# Sensors.net
KiCad netlist of a schematic drawn in Altium Designer
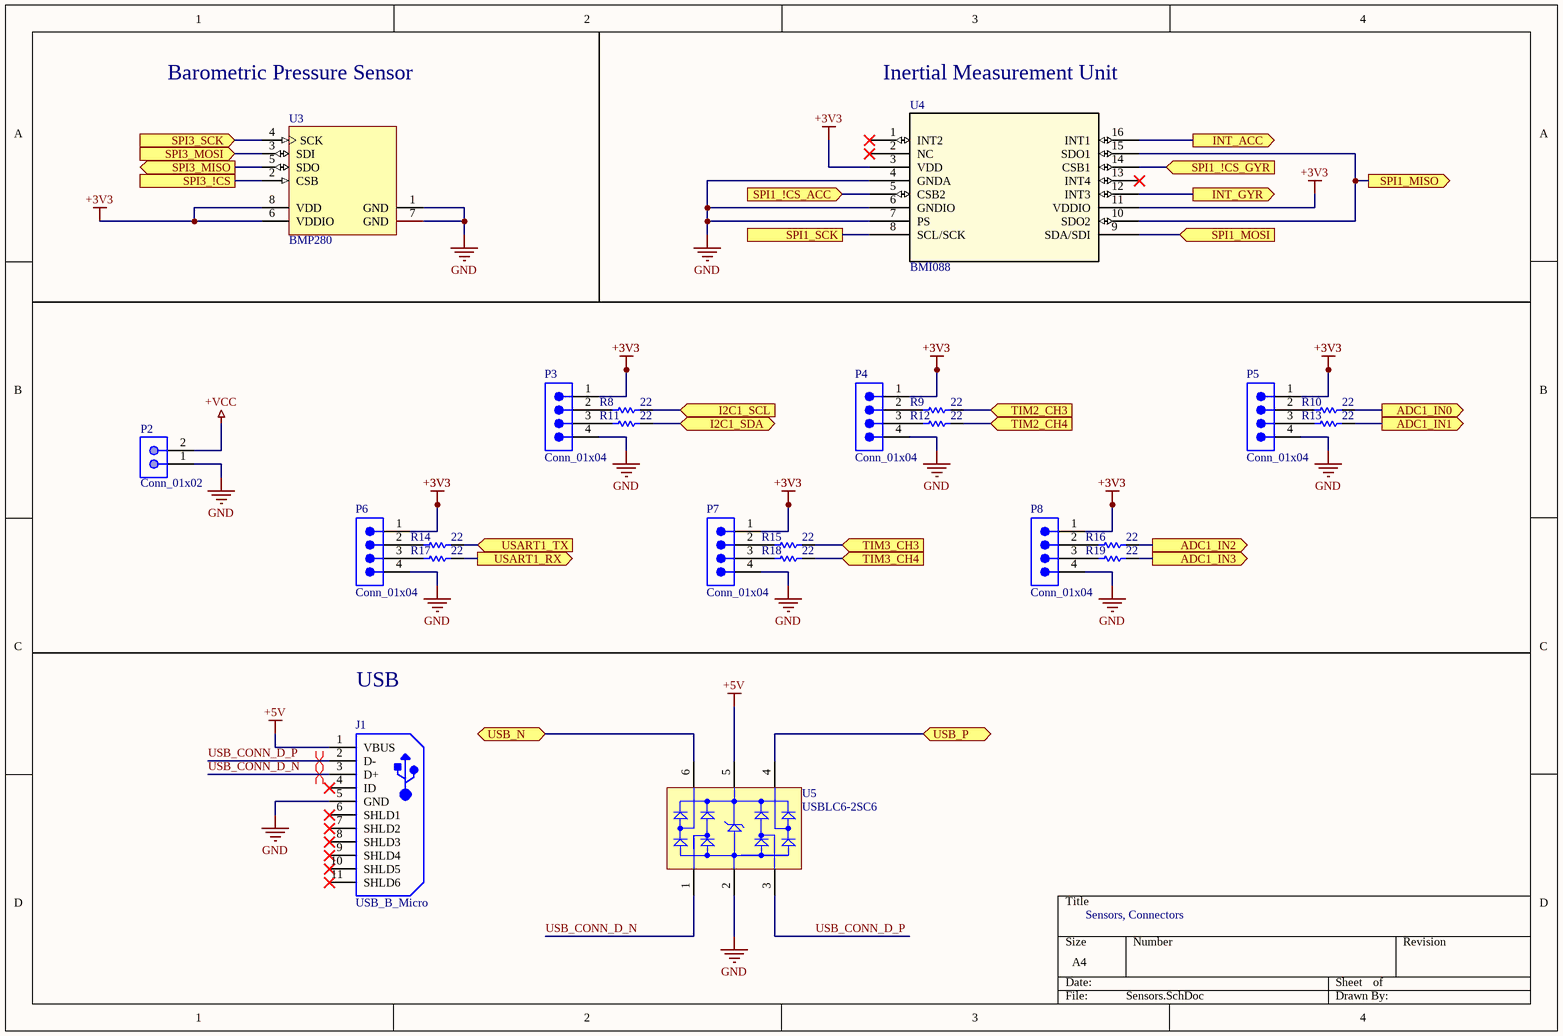
[diagram p0: Sensors.SchDoc]

(export (version "E")
  (design (tool "Eeschema 10.0.6"))
  (components
    (comp (ref "J1")
      (value "USB_B_Micro")
      (footprint "MOLX-105133-0001_V")
      (description "Micro USB B Type Receptacle, -55 to 85 degC, 5-Pin SMD, RoHS, Tape and Reel")
      (fields
        (field (name "MANUFACTURER") "Amphenol FCI")
        (field (name "MANUFACTURER PART NUMBER") "10118193-0001LF")
      )
      (libsource (lib "F4_Flight_Controller") (part "USB_B_Micro"))
    )
    (comp (ref "P2")
      (value "Conn_01x02")
      (footprint "HDRV10W90P254_1X2_1270X483X840P")
      (fields
        (field (name "MANUFACTURER") "TE Connectivity")
        (field (name "MANUFACTURER PART NUMBER") "5-146280-2")
      )
      (libsource (lib "F4_Flight_Controller") (part "Male Header 01x02"))
    )
    (comp (ref "P3")
      (value "Conn_01x04")
      (footprint "HDRV10W90P254_1X4_1270X483X840P")
      (description "Horizontal Surface Mount Header, -55 to 125 degC, 2 mm Pitch, 4-Pin, Male, RoHS")
      (fields (field (name "PARTNUMBER") "MMT-104-01-L-SH") (field (name "MANUFACTURER") "Samtec"))
      (libsource (lib "F4_Flight_Controller") (part "Male Header 01x04"))
    )
    (comp (ref "P4")
      (value "Conn_01x04")
      (footprint "HDRV10W90P254_1X4_1270X483X840P")
      (description "Horizontal Surface Mount Header, -55 to 125 degC, 2 mm Pitch, 4-Pin, Male, RoHS")
      (fields (field (name "PARTNUMBER") "MMT-104-01-L-SH") (field (name "MANUFACTURER") "Samtec"))
      (libsource (lib "F4_Flight_Controller") (part "Male Header 01x04"))
    )
    (comp (ref "P5")
      (value "Conn_01x04")
      (footprint "HDRV10W90P254_1X4_1270X483X840P")
      (description "Horizontal Surface Mount Header, -55 to 125 degC, 2 mm Pitch, 4-Pin, Male, RoHS")
      (fields (field (name "PARTNUMBER") "MMT-104-01-L-SH") (field (name "MANUFACTURER") "Samtec"))
      (libsource (lib "F4_Flight_Controller") (part "Male Header 01x04"))
    )
    (comp (ref "P6")
      (value "Conn_01x04")
      (footprint "HDRV10W90P254_1X4_1270X483X840P")
      (description "Horizontal Surface Mount Header, -55 to 125 degC, 2 mm Pitch, 4-Pin, Male, RoHS")
      (fields (field (name "PARTNUMBER") "MMT-104-01-L-SH") (field (name "MANUFACTURER") "Samtec"))
      (libsource (lib "F4_Flight_Controller") (part "Male Header 01x04"))
    )
    (comp (ref "P7")
      (value "Conn_01x04")
      (footprint "HDRV10W90P254_1X4_1270X483X840P")
      (description "Horizontal Surface Mount Header, -55 to 125 degC, 2 mm Pitch, 4-Pin, Male, RoHS")
      (fields (field (name "PARTNUMBER") "MMT-104-01-L-SH") (field (name "MANUFACTURER") "Samtec"))
      (libsource (lib "F4_Flight_Controller") (part "Male Header 01x04"))
    )
    (comp (ref "P8")
      (value "Conn_01x04")
      (footprint "HDRV10W90P254_1X4_1270X483X840P")
      (description "Horizontal Surface Mount Header, -55 to 125 degC, 2 mm Pitch, 4-Pin, Male, RoHS")
      (fields (field (name "PARTNUMBER") "MMT-104-01-L-SH") (field (name "MANUFACTURER") "Samtec"))
      (libsource (lib "F4_Flight_Controller") (part "Male Header 01x04"))
    )
    (comp (ref "R8")
      (value "22")
      (footprint "Resistor 0402")
      (description "Chip Resistor 0402")
      (fields (field (name "MANUFACTURER") "Vishay") (field (name "PART NUMBER") "CRCW0402120RFKED"))
      (libsource (lib "F4_Flight_Controller") (part "Resistor 0402"))
    )
    (comp (ref "R9")
      (value "22")
      (footprint "Resistor 0402")
      (description "Chip Resistor 0402")
      (fields (field (name "MANUFACTURER") "Vishay") (field (name "PART NUMBER") "CRCW0402120RFKED"))
      (libsource (lib "F4_Flight_Controller") (part "Resistor 0402"))
    )
    (comp (ref "R10")
      (value "22")
      (footprint "Resistor 0402")
      (description "Chip Resistor 0402")
      (fields (field (name "MANUFACTURER") "Vishay") (field (name "PART NUMBER") "CRCW0402120RFKED"))
      (libsource (lib "F4_Flight_Controller") (part "Resistor 0402"))
    )
    (comp (ref "R11")
      (value "22")
      (footprint "Resistor 0402")
      (description "Chip Resistor 0402")
      (fields (field (name "MANUFACTURER") "Vishay") (field (name "PART NUMBER") "CRCW0402120RFKED"))
      (libsource (lib "F4_Flight_Controller") (part "Resistor 0402"))
    )
    (comp (ref "R12")
      (value "22")
      (footprint "Resistor 0402")
      (description "Chip Resistor 0402")
      (fields (field (name "MANUFACTURER") "Vishay") (field (name "PART NUMBER") "CRCW0402120RFKED"))
      (libsource (lib "F4_Flight_Controller") (part "Resistor 0402"))
    )
    (comp (ref "R13")
      (value "22")
      (footprint "Resistor 0402")
      (description "Chip Resistor 0402")
      (fields (field (name "MANUFACTURER") "Vishay") (field (name "PART NUMBER") "CRCW0402120RFKED"))
      (libsource (lib "F4_Flight_Controller") (part "Resistor 0402"))
    )
    (comp (ref "R14")
      (value "22")
      (footprint "Resistor 0402")
      (description "Chip Resistor 0402")
      (fields (field (name "MANUFACTURER") "Vishay") (field (name "PART NUMBER") "CRCW0402120RFKED"))
      (libsource (lib "F4_Flight_Controller") (part "Resistor 0402"))
    )
    (comp (ref "R15")
      (value "22")
      (footprint "Resistor 0402")
      (description "Chip Resistor 0402")
      (fields (field (name "MANUFACTURER") "Vishay") (field (name "PART NUMBER") "CRCW0402120RFKED"))
      (libsource (lib "F4_Flight_Controller") (part "Resistor 0402"))
    )
    (comp (ref "R16")
      (value "22")
      (footprint "Resistor 0402")
      (description "Chip Resistor 0402")
      (fields (field (name "MANUFACTURER") "Vishay") (field (name "PART NUMBER") "CRCW0402120RFKED"))
      (libsource (lib "F4_Flight_Controller") (part "Resistor 0402"))
    )
    (comp (ref "R17")
      (value "22")
      (footprint "Resistor 0402")
      (description "Chip Resistor 0402")
      (fields (field (name "MANUFACTURER") "Vishay") (field (name "PART NUMBER") "CRCW0402120RFKED"))
      (libsource (lib "F4_Flight_Controller") (part "Resistor 0402"))
    )
    (comp (ref "R18")
      (value "22")
      (footprint "Resistor 0402")
      (description "Chip Resistor 0402")
      (fields (field (name "MANUFACTURER") "Vishay") (field (name "PART NUMBER") "CRCW0402120RFKED"))
      (libsource (lib "F4_Flight_Controller") (part "Resistor 0402"))
    )
    (comp (ref "R19")
      (value "22")
      (footprint "Resistor 0402")
      (description "Chip Resistor 0402")
      (fields (field (name "MANUFACTURER") "Vishay") (field (name "PART NUMBER") "CRCW0402120RFKED"))
      (libsource (lib "F4_Flight_Controller") (part "Resistor 0402"))
    )
    (comp (ref "U3")
      (value "BMP280")
      (footprint "8-PIN-METAL-LID-LGA")
      (description "Digital Pressure Sensor,")
      (fields (field (name "MANUFACTURER") "Bosch"))
      (libsource (lib "F4_Flight_Controller") (part "BMP280"))
    )
    (comp (ref "U4")
      (value "BMI088")
      (footprint "BMI088")
      (description "Inertial Measurement Unit BOSCH")
      (fields (field (name "COPYRIGHT") "Copyright (C) 2018 Accelerated Designs. All rights reserved"))
      (libsource (lib "F4_Flight_Controller") (part "BMI088"))
    )
    (comp (ref "U5")
      (value "USBLC6-2SC6")
      (footprint "SOT95P280X145-6N")
      (description "Very low capacitance ESD protection, 3.5 pF, -40 to 125 degC, 6-Pin SOT23, RoHS, Tape and Reel")
      (fields (field (name "MANUFACTURER") "STMicroelectronics"))
      (libsource (lib "F4_Flight_Controller") (part "ESD protection"))
    )
  )
  (nets
    (net (code "1") (name "+3V3") (class "Default")
      (node (ref "P3") (pin "1") (pinfunction "1_1") (pintype "passive"))
      (node (ref "P4") (pin "1") (pinfunction "1_1") (pintype "passive"))
      (node (ref "P5") (pin "1") (pinfunction "1_1") (pintype "passive"))
      (node (ref "P6") (pin "1") (pinfunction "1_1") (pintype "passive"))
      (node (ref "P7") (pin "1") (pinfunction "1_1") (pintype "passive"))
      (node (ref "P8") (pin "1") (pinfunction "1_1") (pintype "passive"))
      (node (ref "U3") (pin "6") (pinfunction "VDDIO_6") (pintype "power_in"))
      (node (ref "U3") (pin "8") (pinfunction "VDD_8") (pintype "power_in"))
      (node (ref "U4") (pin "11") (pinfunction "VDDIO_11") (pintype "power_in"))
      (node (ref "U4") (pin "3") (pinfunction "VDD_3") (pintype "power_in"))
    )
    (net (code "2") (name "+5V") (class "Default")
      (node (ref "J1") (pin "1") (pinfunction "VBUS_1") (pintype "passive"))
      (node (ref "U5") (pin "5") (pinfunction "VBUS_5") (pintype "passive"))
    )
    (net (code "3") (name "+VCC") (class "Default")
      (node (ref "P2") (pin "2") (pinfunction "2_2") (pintype "passive"))
    )
    (net (code "4") (name "/ADC1_IN0") (class "Default")
      (node (ref "R10") (pin "1") (pinfunction "1_1") (pintype "passive"))
    )
    (net (code "5") (name "/ADC1_IN1") (class "Default")
      (node (ref "R13") (pin "1") (pinfunction "1_1") (pintype "passive"))
    )
    (net (code "6") (name "/ADC1_IN2") (class "Default")
      (node (ref "R16") (pin "1") (pinfunction "1_1") (pintype "passive"))
    )
    (net (code "7") (name "/ADC1_IN3") (class "Default")
      (node (ref "R19") (pin "1") (pinfunction "1_1") (pintype "passive"))
    )
    (net (code "8") (name "/I2C1_SCL") (class "Default")
      (node (ref "R8") (pin "1") (pinfunction "1_1") (pintype "passive"))
    )
    (net (code "9") (name "/I2C1_SDA") (class "Default")
      (node (ref "R11") (pin "1") (pinfunction "1_1") (pintype "passive"))
    )
    (net (code "10") (name "/INT_ACC") (class "Default")
      (node (ref "U4") (pin "16") (pinfunction "INT1_16") (pintype "bidirectional"))
    )
    (net (code "11") (name "/INT_GYR") (class "Default")
      (node (ref "U4") (pin "12") (pinfunction "INT3_12") (pintype "bidirectional"))
    )
    (net (code "12") (name "/SPI1_!CS_ACC") (class "Default")
      (node (ref "U4") (pin "5") (pinfunction "CSB2_5") (pintype "bidirectional"))
    )
    (net (code "13") (name "/SPI1_!CS_GYR") (class "Default")
      (node (ref "U4") (pin "14") (pinfunction "CSB1_14") (pintype "bidirectional"))
    )
    (net (code "14") (name "/SPI1_MISO") (class "Default")
      (node (ref "U4") (pin "10") (pinfunction "SDO2_10") (pintype "bidirectional"))
      (node (ref "U4") (pin "15") (pinfunction "SDO1_15") (pintype "bidirectional"))
    )
    (net (code "15") (name "/SPI1_MOSI") (class "Default")
      (node (ref "U4") (pin "9") (pinfunction "SDA/SDI_9") (pintype "passive"))
    )
    (net (code "16") (name "/SPI1_SCK") (class "Default")
      (node (ref "U4") (pin "8") (pinfunction "SCL/SCK_8") (pintype "passive"))
    )
    (net (code "17") (name "/SPI3_!CS") (class "Default")
      (node (ref "U3") (pin "2") (pinfunction "CSB_2") (pintype "input"))
    )
    (net (code "18") (name "/SPI3_MISO") (class "Default")
      (node (ref "U3") (pin "5") (pinfunction "SDO_5") (pintype "bidirectional"))
    )
    (net (code "19") (name "/SPI3_MOSI") (class "Default")
      (node (ref "U3") (pin "3") (pinfunction "SDI_3") (pintype "bidirectional"))
    )
    (net (code "20") (name "/SPI3_SCK") (class "Default")
      (node (ref "U3") (pin "4") (pinfunction "SCK_4") (pintype "input"))
    )
    (net (code "21") (name "/TIM2_CH3") (class "Default")
      (node (ref "R9") (pin "1") (pinfunction "1_1") (pintype "passive"))
    )
    (net (code "22") (name "/TIM2_CH4") (class "Default")
      (node (ref "R12") (pin "1") (pinfunction "1_1") (pintype "passive"))
    )
    (net (code "23") (name "/TIM3_CH3") (class "Default")
      (node (ref "R15") (pin "1") (pinfunction "1_1") (pintype "passive"))
    )
    (net (code "24") (name "/TIM3_CH4") (class "Default")
      (node (ref "R18") (pin "1") (pinfunction "1_1") (pintype "passive"))
    )
    (net (code "25") (name "/USART1_RX") (class "Default")
      (node (ref "R17") (pin "1") (pinfunction "1_1") (pintype "passive"))
    )
    (net (code "26") (name "/USART1_TX") (class "Default")
      (node (ref "R14") (pin "1") (pinfunction "1_1") (pintype "passive"))
    )
    (net (code "27") (name "/USB_CONN_D_N") (class "Default")
      (node (ref "J1") (pin "3") (pinfunction "D+_3") (pintype "passive"))
      (node (ref "U5") (pin "1") (pinfunction "I/O_1_1") (pintype "passive"))
    )
    (net (code "28") (name "/USB_CONN_D_P") (class "Default")
      (node (ref "J1") (pin "2") (pinfunction "D-_2") (pintype "passive"))
      (node (ref "U5") (pin "3") (pinfunction "I/O_2_3") (pintype "passive"))
    )
    (net (code "29") (name "/USB_N") (class "Default")
      (node (ref "U5") (pin "6") (pinfunction "I/O_4_6") (pintype "passive"))
    )
    (net (code "30") (name "/USB_P") (class "Default")
      (node (ref "U5") (pin "4") (pinfunction "I/O_3_4") (pintype "passive"))
    )
    (net (code "31") (name "GND") (class "Default")
      (node (ref "J1") (pin "5") (pinfunction "GND_5") (pintype "passive"))
      (node (ref "P2") (pin "1") (pinfunction "1_1") (pintype "passive"))
      (node (ref "P3") (pin "4") (pinfunction "4_4") (pintype "passive"))
      (node (ref "P4") (pin "4") (pinfunction "4_4") (pintype "passive"))
      (node (ref "P5") (pin "4") (pinfunction "4_4") (pintype "passive"))
      (node (ref "P6") (pin "4") (pinfunction "4_4") (pintype "passive"))
      (node (ref "P7") (pin "4") (pinfunction "4_4") (pintype "passive"))
      (node (ref "P8") (pin "4") (pinfunction "4_4") (pintype "passive"))
      (node (ref "U3") (pin "1") (pinfunction "GND_1") (pintype "power_in"))
      (node (ref "U3") (pin "7") (pinfunction "GND_7") (pintype "power_in"))
      (node (ref "U4") (pin "4") (pinfunction "GNDA_4") (pintype "passive"))
      (node (ref "U4") (pin "6") (pinfunction "GNDIO_6") (pintype "passive"))
      (node (ref "U4") (pin "7") (pinfunction "PS_7") (pintype "passive"))
      (node (ref "U5") (pin "2") (pinfunction "GND_2") (pintype "passive"))
    )
    (net (code "32") (name "Net-(P3-Pad2)") (class "Default")
      (node (ref "P3") (pin "2") (pinfunction "2_2") (pintype "passive"))
      (node (ref "R8") (pin "2") (pinfunction "2_2") (pintype "passive"))
    )
    (net (code "33") (name "Net-(P3-Pad3)") (class "Default")
      (node (ref "P3") (pin "3") (pinfunction "3_3") (pintype "passive"))
      (node (ref "R11") (pin "2") (pinfunction "2_2") (pintype "passive"))
    )
    (net (code "34") (name "Net-(P4-Pad2)") (class "Default")
      (node (ref "P4") (pin "2") (pinfunction "2_2") (pintype "passive"))
      (node (ref "R9") (pin "2") (pinfunction "2_2") (pintype "passive"))
    )
    (net (code "35") (name "Net-(P4-Pad3)") (class "Default")
      (node (ref "P4") (pin "3") (pinfunction "3_3") (pintype "passive"))
      (node (ref "R12") (pin "2") (pinfunction "2_2") (pintype "passive"))
    )
    (net (code "36") (name "Net-(P5-Pad2)") (class "Default")
      (node (ref "P5") (pin "2") (pinfunction "2_2") (pintype "passive"))
      (node (ref "R10") (pin "2") (pinfunction "2_2") (pintype "passive"))
    )
    (net (code "37") (name "Net-(P5-Pad3)") (class "Default")
      (node (ref "P5") (pin "3") (pinfunction "3_3") (pintype "passive"))
      (node (ref "R13") (pin "2") (pinfunction "2_2") (pintype "passive"))
    )
    (net (code "38") (name "Net-(P6-Pad2)") (class "Default")
      (node (ref "P6") (pin "2") (pinfunction "2_2") (pintype "passive"))
      (node (ref "R14") (pin "2") (pinfunction "2_2") (pintype "passive"))
    )
    (net (code "39") (name "Net-(P6-Pad3)") (class "Default")
      (node (ref "P6") (pin "3") (pinfunction "3_3") (pintype "passive"))
      (node (ref "R17") (pin "2") (pinfunction "2_2") (pintype "passive"))
    )
    (net (code "40") (name "Net-(P7-Pad2)") (class "Default")
      (node (ref "P7") (pin "2") (pinfunction "2_2") (pintype "passive"))
      (node (ref "R15") (pin "2") (pinfunction "2_2") (pintype "passive"))
    )
    (net (code "41") (name "Net-(P7-Pad3)") (class "Default")
      (node (ref "P7") (pin "3") (pinfunction "3_3") (pintype "passive"))
      (node (ref "R18") (pin "2") (pinfunction "2_2") (pintype "passive"))
    )
    (net (code "42") (name "Net-(P8-Pad2)") (class "Default")
      (node (ref "P8") (pin "2") (pinfunction "2_2") (pintype "passive"))
      (node (ref "R16") (pin "2") (pinfunction "2_2") (pintype "passive"))
    )
    (net (code "43") (name "Net-(P8-Pad3)") (class "Default")
      (node (ref "P8") (pin "3") (pinfunction "3_3") (pintype "passive"))
      (node (ref "R19") (pin "2") (pinfunction "2_2") (pintype "passive"))
    )
    (net (code "44") (name "unconnected-(J1-ID-Pad4)") (class "Default")
      (node (ref "J1") (pin "4") (pinfunction "ID_4") (pintype "passive+no_connect"))
    )
    (net (code "45") (name "unconnected-(J1-SHLD1-Pad6)") (class "Default")
      (node (ref "J1") (pin "6") (pinfunction "SHLD1_6") (pintype "passive+no_connect"))
    )
    (net (code "46") (name "unconnected-(J1-SHLD2-Pad7)") (class "Default")
      (node (ref "J1") (pin "7") (pinfunction "SHLD2_7") (pintype "passive+no_connect"))
    )
    (net (code "47") (name "unconnected-(J1-SHLD3-Pad8)") (class "Default")
      (node (ref "J1") (pin "8") (pinfunction "SHLD3_8") (pintype "passive+no_connect"))
    )
    (net (code "48") (name "unconnected-(J1-SHLD4-Pad9)") (class "Default")
      (node (ref "J1") (pin "9") (pinfunction "SHLD4_9") (pintype "passive+no_connect"))
    )
    (net (code "49") (name "unconnected-(J1-SHLD5-Pad10)") (class "Default")
      (node (ref "J1") (pin "10") (pinfunction "SHLD5_10") (pintype "passive+no_connect"))
    )
    (net (code "50") (name "unconnected-(J1-SHLD6-Pad11)") (class "Default")
      (node (ref "J1") (pin "11") (pinfunction "SHLD6_11") (pintype "passive+no_connect"))
    )
    (net (code "51") (name "unconnected-(U4-INT2-Pad1)") (class "Default")
      (node (ref "U4") (pin "1") (pinfunction "INT2_1") (pintype "bidirectional+no_connect"))
    )
    (net (code "52") (name "unconnected-(U4-INT4-Pad13)") (class "Default")
      (node (ref "U4") (pin "13") (pinfunction "INT4_13") (pintype "bidirectional+no_connect"))
    )
    (net (code "53") (name "unconnected-(U4-NC-Pad2)") (class "Default")
      (node (ref "U4") (pin "2") (pinfunction "NC_2") (pintype "passive+no_connect"))
    )
  )
)
